# MainPowerBoard.net
KiCad netlist of a schematic drawn in Altium Designer
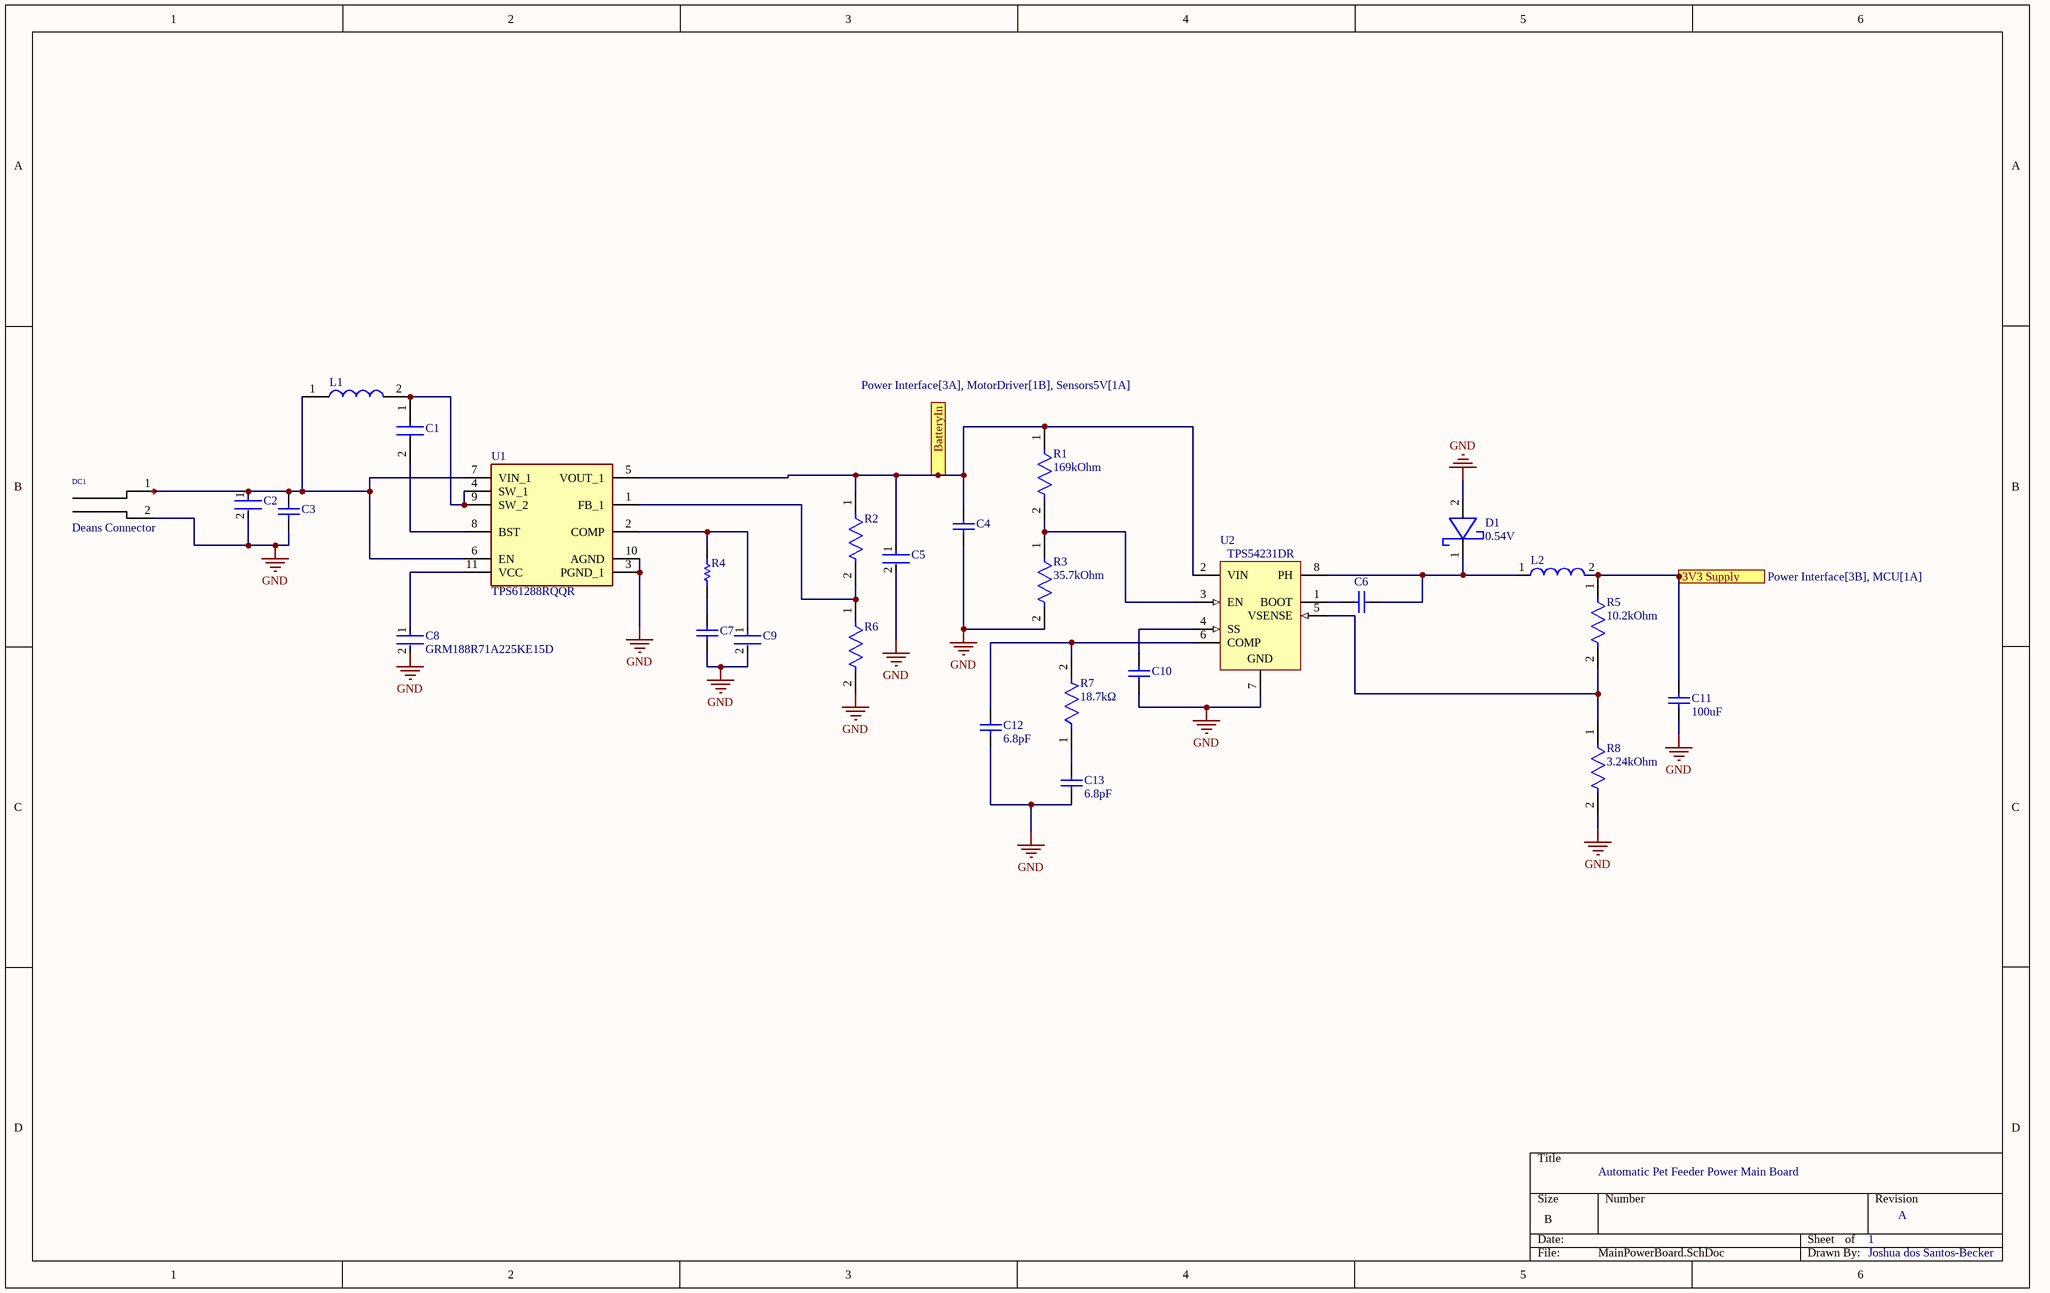
[diagram p0: MainPowerBoard.SchDoc]

(export (version "E")
  (design (tool "Eeschema 10.0.6"))
  (components
    (comp (ref "C1")
      (value "EMK107B7104KA-T")
      (footprint "gfl:CAPC1608X95N")
      (description "Capacitor")
      (fields (field (name "MOUSER PART NUMBER") "963-EMK107B7104KA-T"))
      (libsource (lib "*") (part "EMK107B7104KA-T"))
    )
    (comp (ref "C2")
      (value "GRM188R60J106ME47D")
      (footprint "FP-GRM188-0_1-e0_2_0_55-IPC_A")
      (description "Chip Multilayer Ceramic Capacitors for General Purpose, 0603, 10uF, X5R, 15%, 20%, 6.3V")
      (fields (field (name "VOLTAGE") "6.3V") (field (name "TOLERANCE") "20%"))
      (libsource (lib "Altium Content Vault") (part "02cd4be3c70576c341d710602a673aa"))
    )
    (comp (ref "C3")
      (value "GRM188R71H104KA93D")
      (footprint "CAPC1608X90X35ML10T15")
      (description "Chip Capacitor, 0.1 uF, +/- 10%, 50 V, -55 to 125 degC, 0603 (1608 Metric), RoHS, Tape and Reel")
      (fields (field (name "TOLERANCE") "10%") (field (name "VOLTAGE") "50V"))
      (libsource (lib "Altium Content Vault") (part "CAP-NP-2"))
    )
    (comp (ref "C4")
      (value "~")
      (footprint "FP-GRM32-IPC_A")
      (description "GRM32ER61E226KE15L")
      (fields
        (field (name "TOLERANCE") "10%")
        (field (name "MANUFACTURER") "Murata Electronics North America")
      )
      (libsource (lib "gsl") (part "Cin"))
    )
    (comp (ref "C5")
      (value "GRM32ER61C476KE15L")
      (footprint "FP-GRM32E-0_3-0_2-IPC_C")
      (description "CAP CER 47UF 16V X5R 1210")
      (fields (field (name "VOLTAGE") "16V") (field (name "TOLERANCE") "10%"))
      (libsource (lib "Altium Content Vault") (part "b4654b650e69147ec39a6b967a45e02"))
    )
    (comp (ref "C6")
      (value "~")
      (footprint "CAPC1005X55X25LL05T10")
      (description "GRM155R71A104KA01D")
      (fields (field (name "MANUFACTURER") "Murata"))
      (libsource (lib "gsl") (part "Cboot"))
    )
    (comp (ref "C7")
      (value "GRM155R61A393KA01D")
      (footprint "CAPC1005X55X25NL05T10")
      (fields (field (name "MANUFACTURER") "Murata"))
      (libsource (lib "Altium Content Vault") (part "CAP"))
    )
    (comp (ref "C8")
      (value "GRM188R71A225KE15D")
      (footprint "FP-GRM188-0_1-e0_2_0_5-MFG")
      (description "Chip Multilayer Ceramic Capacitors for General Purpose, 0603, 2.2uF, X7R, 15%, 10%, 10V")
      (fields (field (name "VOLTAGE") "10V") (field (name "TOLERANCE") "10%"))
      (libsource (lib "Altium Content Vault") (part "11868f565c42a9108669ba33697ecf6"))
    )
    (comp (ref "C9")
      (value "CL21C101JBANNNC")
      (footprint "FP-CL21-IPC_C")
      (description "CL21 Series 0805 100pF 50V ±5% Tolerance C0G Multilayer Ceramic Chip Capacitor")
      (fields (field (name "VOLTAGE") "50V") (field (name "TOLERANCE") "5%"))
      (libsource (lib "Altium Content Vault") (part "b4654b650e69147ec39a6b967a45e02"))
    )
    (comp (ref "C10")
      (value "~")
      (footprint "CAPC1005X55X25LL05T10")
      (description "GRM155R71C822KA01D")
      (fields (field (name "MANUFACTURER") "Murata"))
      (libsource (lib "gsl") (part "CSS"))
    )
    (comp (ref "C11")
      (value "100uF")
      (footprint "CAP_0805")
      (description "Capacitor SMD 0805 Generic")
      (libsource (lib "gsl") (part "CAP_0805"))
    )
    (comp (ref "C12")
      (value "6.8pF")
      (footprint "Ccomp2")
      (description "06031U6R8BAT2A")
      (libsource (lib "gsl") (part "Ccomp2"))
    )
    (comp (ref "C13")
      (value "6.8pF")
      (footprint "Ccomp")
      (description "06031U6R8BAT2A")
      (libsource (lib "gsl") (part "Ccomp"))
    )
    (comp (ref "D1") (value "0.54V") (footprint "SODFL260X100-2N") (libsource (lib "gsl") (part "Schottky")))
    (comp (ref "DC1")
      (value "Deans Connector")
      (footprint "Deans")
      (libsource (lib "gsl") (part "Deans Connector"))
    )
    (comp (ref "L1")
      (value "XAL7070-222MEB")
      (footprint "XAL7070332MEB")
      (description "Inductor")
      (fields (field (name "MOUSER PART NUMBER") "994-XAL7070-222MEB"))
      (libsource (lib "*") (part "XAL7070-222MEB"))
    )
    (comp (ref "L2")
      (value "~")
      (footprint "WE-TI-L")
      (description "744772390")
      (libsource (lib "gsl") (part "PAS-IND-INDUCTOR-2"))
    )
    (comp (ref "R1")
      (value "169kOhm")
      (footprint "FP-CRCW0402-e3-IPC_B")
      (description "CRCW0402169KFKED")
      (fields (field (name "TOLERANCE") "1%"))
      (libsource (lib "Altium Content Vault") (part "1029c3af85768c4190bb7ad29bc67b5"))
    )
    (comp (ref "R2")
      (value "CRCW0805931KFKEA")
      (footprint "gfl:RESC2012X50N")
      (description "Resistor")
      (fields (field (name "MOUSER PART NUMBER") "71-CRCW0805-931K-E3"))
      (libsource (lib "gsl") (part "CRCW0805931KFKEA"))
    )
    (comp (ref "R3")
      (value "35.7kOhm")
      (footprint "FP-CRCW0402-e3-MFG")
      (description "CRCW040235K7FKED")
      (fields (field (name "TOLERANCE") "1%"))
      (libsource (lib "Altium Content Vault") (part "1029c3af85768c4190bb7ad29bc67b5"))
    )
    (comp (ref "R4")
      (value "CRCW060339K2FKEA")
      (footprint "RESC1609X50X30LL10T20")
      (fields (field (name "MANUFACTURER") "Vishay Dale"))
      (libsource (lib "Altium Content Vault") (part "RES"))
    )
    (comp (ref "R5")
      (value "10.2kOhm")
      (footprint "FP-CRCW0402-e3-MFG")
      (description "CRCW040210K2FKED")
      (fields (field (name "TOLERANCE") "1%"))
      (libsource (lib "Altium Content Vault") (part "1029c3af85768c4190bb7ad29bc67b5"))
    )
    (comp (ref "R6")
      (value "CRCW080548K7FKEA")
      (footprint "FP-CRCW0805-e3-IPC_A")
      (description "RES Thick Film, 48.7kΩ, 1%, 0.125W, 100ppm/°C, 0805")
      (fields (field (name "TOLERANCE") "1%"))
      (libsource (lib "Altium Content Vault") (part "1029c3af85768c4190bb7ad29bc67b5"))
    )
    (comp (ref "R7")
      (value "18.7kΩ")
      (footprint "FP-AC0402-IPC_A")
      (description "AC0402FR-0718K7L")
      (fields (field (name "TOLERANCE") "1%"))
      (libsource (lib "Altium Content Vault") (part "1029c3af85768c4190bb7ad29bc67b5"))
    )
    (comp (ref "R8")
      (value "3.24kOhm")
      (footprint "FP-CRCW0402-e3-MFG")
      (description "CRCW04023K24FKED")
      (fields (field (name "TOLERANCE") "1%"))
      (libsource (lib "Altium Content Vault") (part "1029c3af85768c4190bb7ad29bc67b5"))
    )
    (comp (ref "U1")
      (value "TPS61288RQQR")
      (footprint "TPS61288RQQR")
      (libsource (lib "gsl") (part "TPS61288RQQR"))
    )
    (comp (ref "U2")
      (value "TPS54231DR")
      (footprint "D0008A_L")
      (fields (field (name "MANUFACTURER") "Texas Instruments"))
      (libsource (lib "Altium Content Vault") (part "TI-TPS54231D8"))
    )
  )
  (nets
    (net (code "1") (name "/3V3 Supply") (class "Default")
      (node (ref "C11") (pin "1") (pinfunction "1_1") (pintype "passive"))
      (node (ref "L2") (pin "2") (pinfunction "2_2") (pintype "passive"))
      (node (ref "R5") (pin "1") (pinfunction "1_1") (pintype "passive"))
    )
    (net (code "2") (name "/BatteryIn") (class "Default")
      (node (ref "C4") (pin "2") (pinfunction "2_2") (pintype "passive"))
      (node (ref "C5") (pin "1") (pinfunction "1_1") (pintype "passive"))
      (node (ref "R1") (pin "1") (pinfunction "1_1") (pintype "passive"))
      (node (ref "R2") (pin "1") (pinfunction "1_1") (pintype "passive"))
      (node (ref "U1") (pin "5") (pinfunction "VOUT_1_5") (pintype "passive"))
      (node (ref "U2") (pin "2") (pinfunction "VIN_2") (pintype "power_in"))
    )
    (net (code "3") (name "GND") (class "Default")
      (node (ref "C10") (pin "2") (pinfunction "2_2") (pintype "passive"))
      (node (ref "C11") (pin "2") (pinfunction "2_2") (pintype "passive"))
      (node (ref "C12") (pin "1") (pinfunction "1_1") (pintype "passive"))
      (node (ref "C13") (pin "2") (pinfunction "2_2") (pintype "passive"))
      (node (ref "C2") (pin "2") (pinfunction "2_2") (pintype "passive"))
      (node (ref "C3") (pin "1") (pinfunction "1_1") (pintype "passive"))
      (node (ref "C4") (pin "1") (pinfunction "1_1") (pintype "passive"))
      (node (ref "C5") (pin "2") (pinfunction "2_2") (pintype "passive"))
      (node (ref "C7") (pin "2") (pinfunction "2_2") (pintype "passive"))
      (node (ref "C8") (pin "2") (pinfunction "2_2") (pintype "passive"))
      (node (ref "C9") (pin "2") (pinfunction "2_2") (pintype "passive"))
      (node (ref "D1") (pin "2") (pintype "passive"))
      (node (ref "DC1") (pin "2") (pinfunction "2_2") (pintype "passive"))
      (node (ref "R3") (pin "2") (pinfunction "2_2") (pintype "passive"))
      (node (ref "R6") (pin "2") (pinfunction "2_2") (pintype "passive"))
      (node (ref "R8") (pin "2") (pinfunction "2_2") (pintype "passive"))
      (node (ref "U1") (pin "10") (pinfunction "AGND_10") (pintype "passive"))
      (node (ref "U1") (pin "3") (pinfunction "PGND_1_3") (pintype "passive"))
      (node (ref "U2") (pin "7") (pinfunction "GND_7") (pintype "power_in"))
    )
    (net (code "4") (name "Net-(C7-Pad1)") (class "Default")
      (node (ref "C7") (pin "1") (pinfunction "1_1") (pintype "passive"))
      (node (ref "R4") (pin "2") (pinfunction "2_2") (pintype "passive"))
    )
    (net (code "5") (name "Net-(C13-Pad1)") (class "Default")
      (node (ref "C13") (pin "1") (pinfunction "1_1") (pintype "passive"))
      (node (ref "R7") (pin "1") (pinfunction "1_1") (pintype "passive"))
    )
    (net (code "6") (name "Net-(U1-BST)") (class "Default")
      (node (ref "C1") (pin "2") (pinfunction "2_2") (pintype "passive"))
      (node (ref "U1") (pin "8") (pinfunction "BST_8") (pintype "passive"))
    )
    (net (code "7") (name "Net-(U1-COMP)") (class "Default")
      (node (ref "C9") (pin "1") (pinfunction "1_1") (pintype "passive"))
      (node (ref "R4") (pin "1") (pinfunction "1_1") (pintype "passive"))
      (node (ref "U1") (pin "2") (pinfunction "COMP_2") (pintype "passive"))
    )
    (net (code "8") (name "Net-(U1-EN)") (class "Default")
      (node (ref "C2") (pin "1") (pinfunction "1_1") (pintype "passive"))
      (node (ref "C3") (pin "2") (pinfunction "2_2") (pintype "passive"))
      (node (ref "DC1") (pin "1") (pinfunction "1_1") (pintype "passive"))
      (node (ref "L1") (pin "1") (pinfunction "1_1") (pintype "passive"))
      (node (ref "U1") (pin "6") (pinfunction "EN_6") (pintype "passive"))
      (node (ref "U1") (pin "7") (pinfunction "VIN_1_7") (pintype "passive"))
    )
    (net (code "9") (name "Net-(U1-FB_1)") (class "Default")
      (node (ref "R2") (pin "2") (pinfunction "2_2") (pintype "passive"))
      (node (ref "R6") (pin "1") (pinfunction "1_1") (pintype "passive"))
      (node (ref "U1") (pin "1") (pinfunction "FB_1_1") (pintype "passive"))
    )
    (net (code "10") (name "Net-(U1-SW_1)") (class "Default")
      (node (ref "C1") (pin "1") (pinfunction "1_1") (pintype "passive"))
      (node (ref "L1") (pin "2") (pinfunction "2_2") (pintype "passive"))
      (node (ref "U1") (pin "4") (pinfunction "SW_1_4") (pintype "passive"))
      (node (ref "U1") (pin "9") (pinfunction "SW_2_9") (pintype "passive"))
    )
    (net (code "11") (name "Net-(U1-VCC)") (class "Default")
      (node (ref "C8") (pin "1") (pinfunction "1_1") (pintype "passive"))
      (node (ref "U1") (pin "11") (pinfunction "VCC_11") (pintype "passive"))
    )
    (net (code "12") (name "Net-(U2-BOOT)") (class "Default")
      (node (ref "C6") (pin "1") (pinfunction "1_1") (pintype "passive"))
      (node (ref "U2") (pin "1") (pinfunction "BOOT_1") (pintype "passive"))
    )
    (net (code "13") (name "Net-(U2-COMP)") (class "Default")
      (node (ref "C12") (pin "2") (pinfunction "2_2") (pintype "passive"))
      (node (ref "R7") (pin "2") (pinfunction "2_2") (pintype "passive"))
      (node (ref "U2") (pin "6") (pinfunction "COMP_6") (pintype "passive"))
    )
    (net (code "14") (name "Net-(U2-EN)") (class "Default")
      (node (ref "R1") (pin "2") (pinfunction "2_2") (pintype "passive"))
      (node (ref "R3") (pin "1") (pinfunction "1_1") (pintype "passive"))
      (node (ref "U2") (pin "3") (pinfunction "EN_3") (pintype "input"))
    )
    (net (code "15") (name "Net-(U2-PH)") (class "Default")
      (node (ref "C6") (pin "2") (pinfunction "2_2") (pintype "passive"))
      (node (ref "D1") (pin "1") (pintype "passive"))
      (node (ref "L2") (pin "1") (pinfunction "1_1") (pintype "passive"))
      (node (ref "U2") (pin "8") (pinfunction "PH_8") (pintype "power_in"))
    )
    (net (code "16") (name "Net-(U2-SS)") (class "Default")
      (node (ref "C10") (pin "1") (pinfunction "1_1") (pintype "passive"))
      (node (ref "U2") (pin "4") (pinfunction "SS_4") (pintype "input"))
    )
    (net (code "17") (name "Net-(U2-VSENSE)") (class "Default")
      (node (ref "R5") (pin "2") (pinfunction "2_2") (pintype "passive"))
      (node (ref "R8") (pin "1") (pinfunction "1_1") (pintype "passive"))
      (node (ref "U2") (pin "5") (pinfunction "VSENSE_5") (pintype "input"))
    )
  )
)
